# S7G7_footprint_simplified_w_ethernet.net
KiCad netlist of a schematic drawn in EAGLE
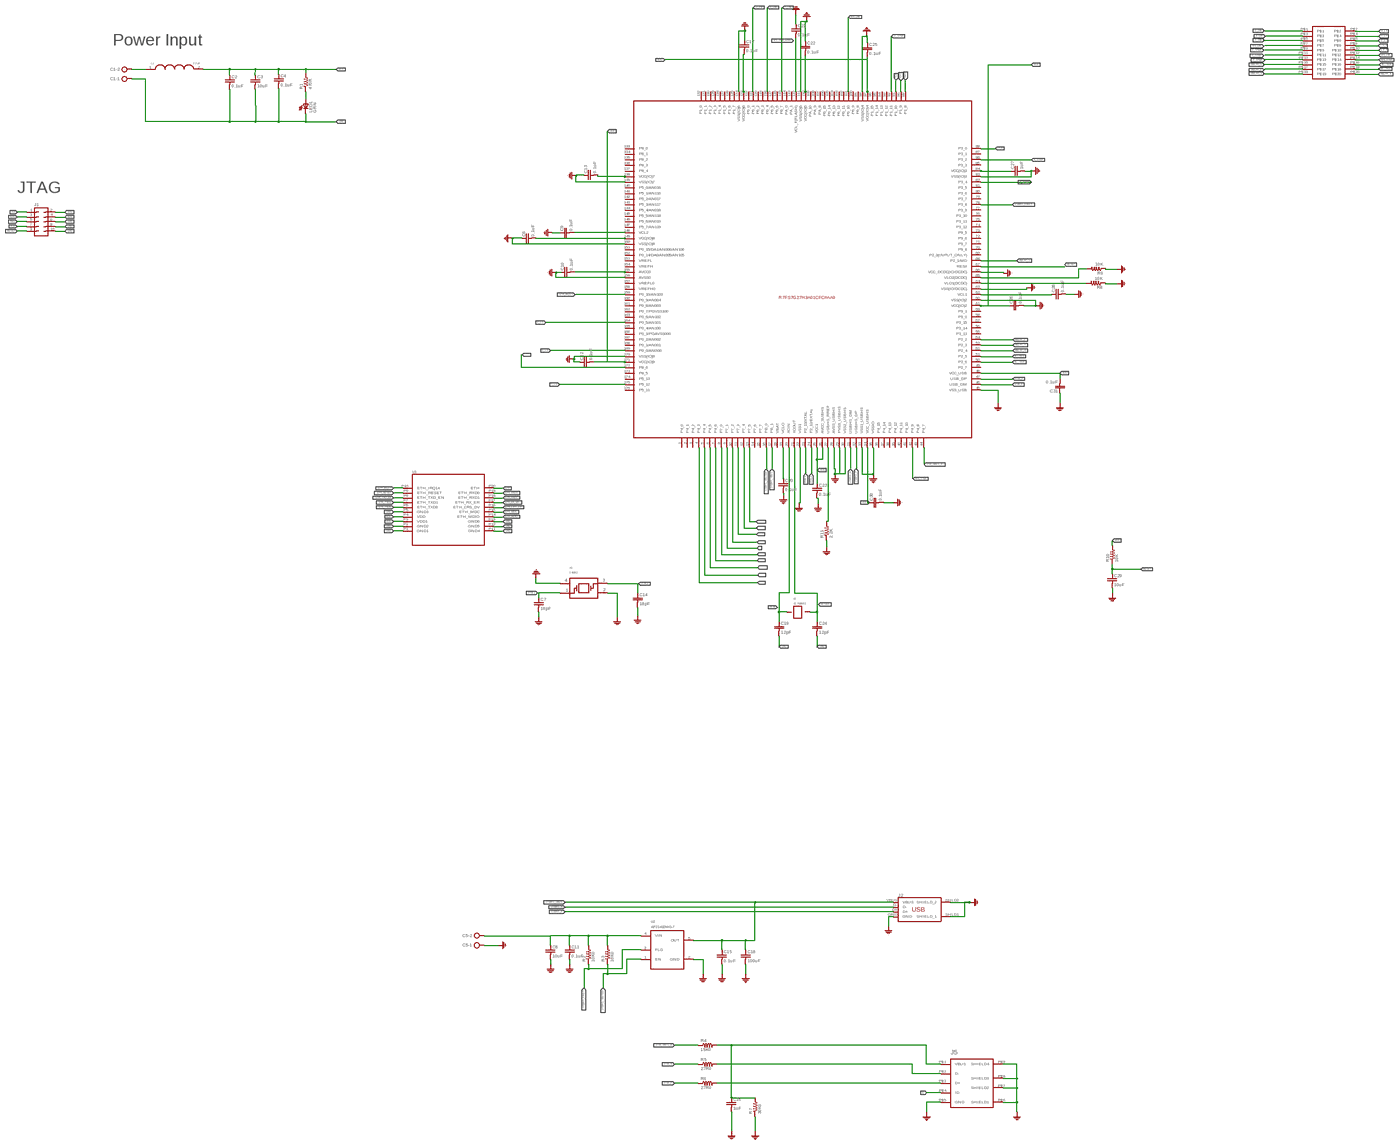
[diagram p0: schematic, sheet 1, overview]
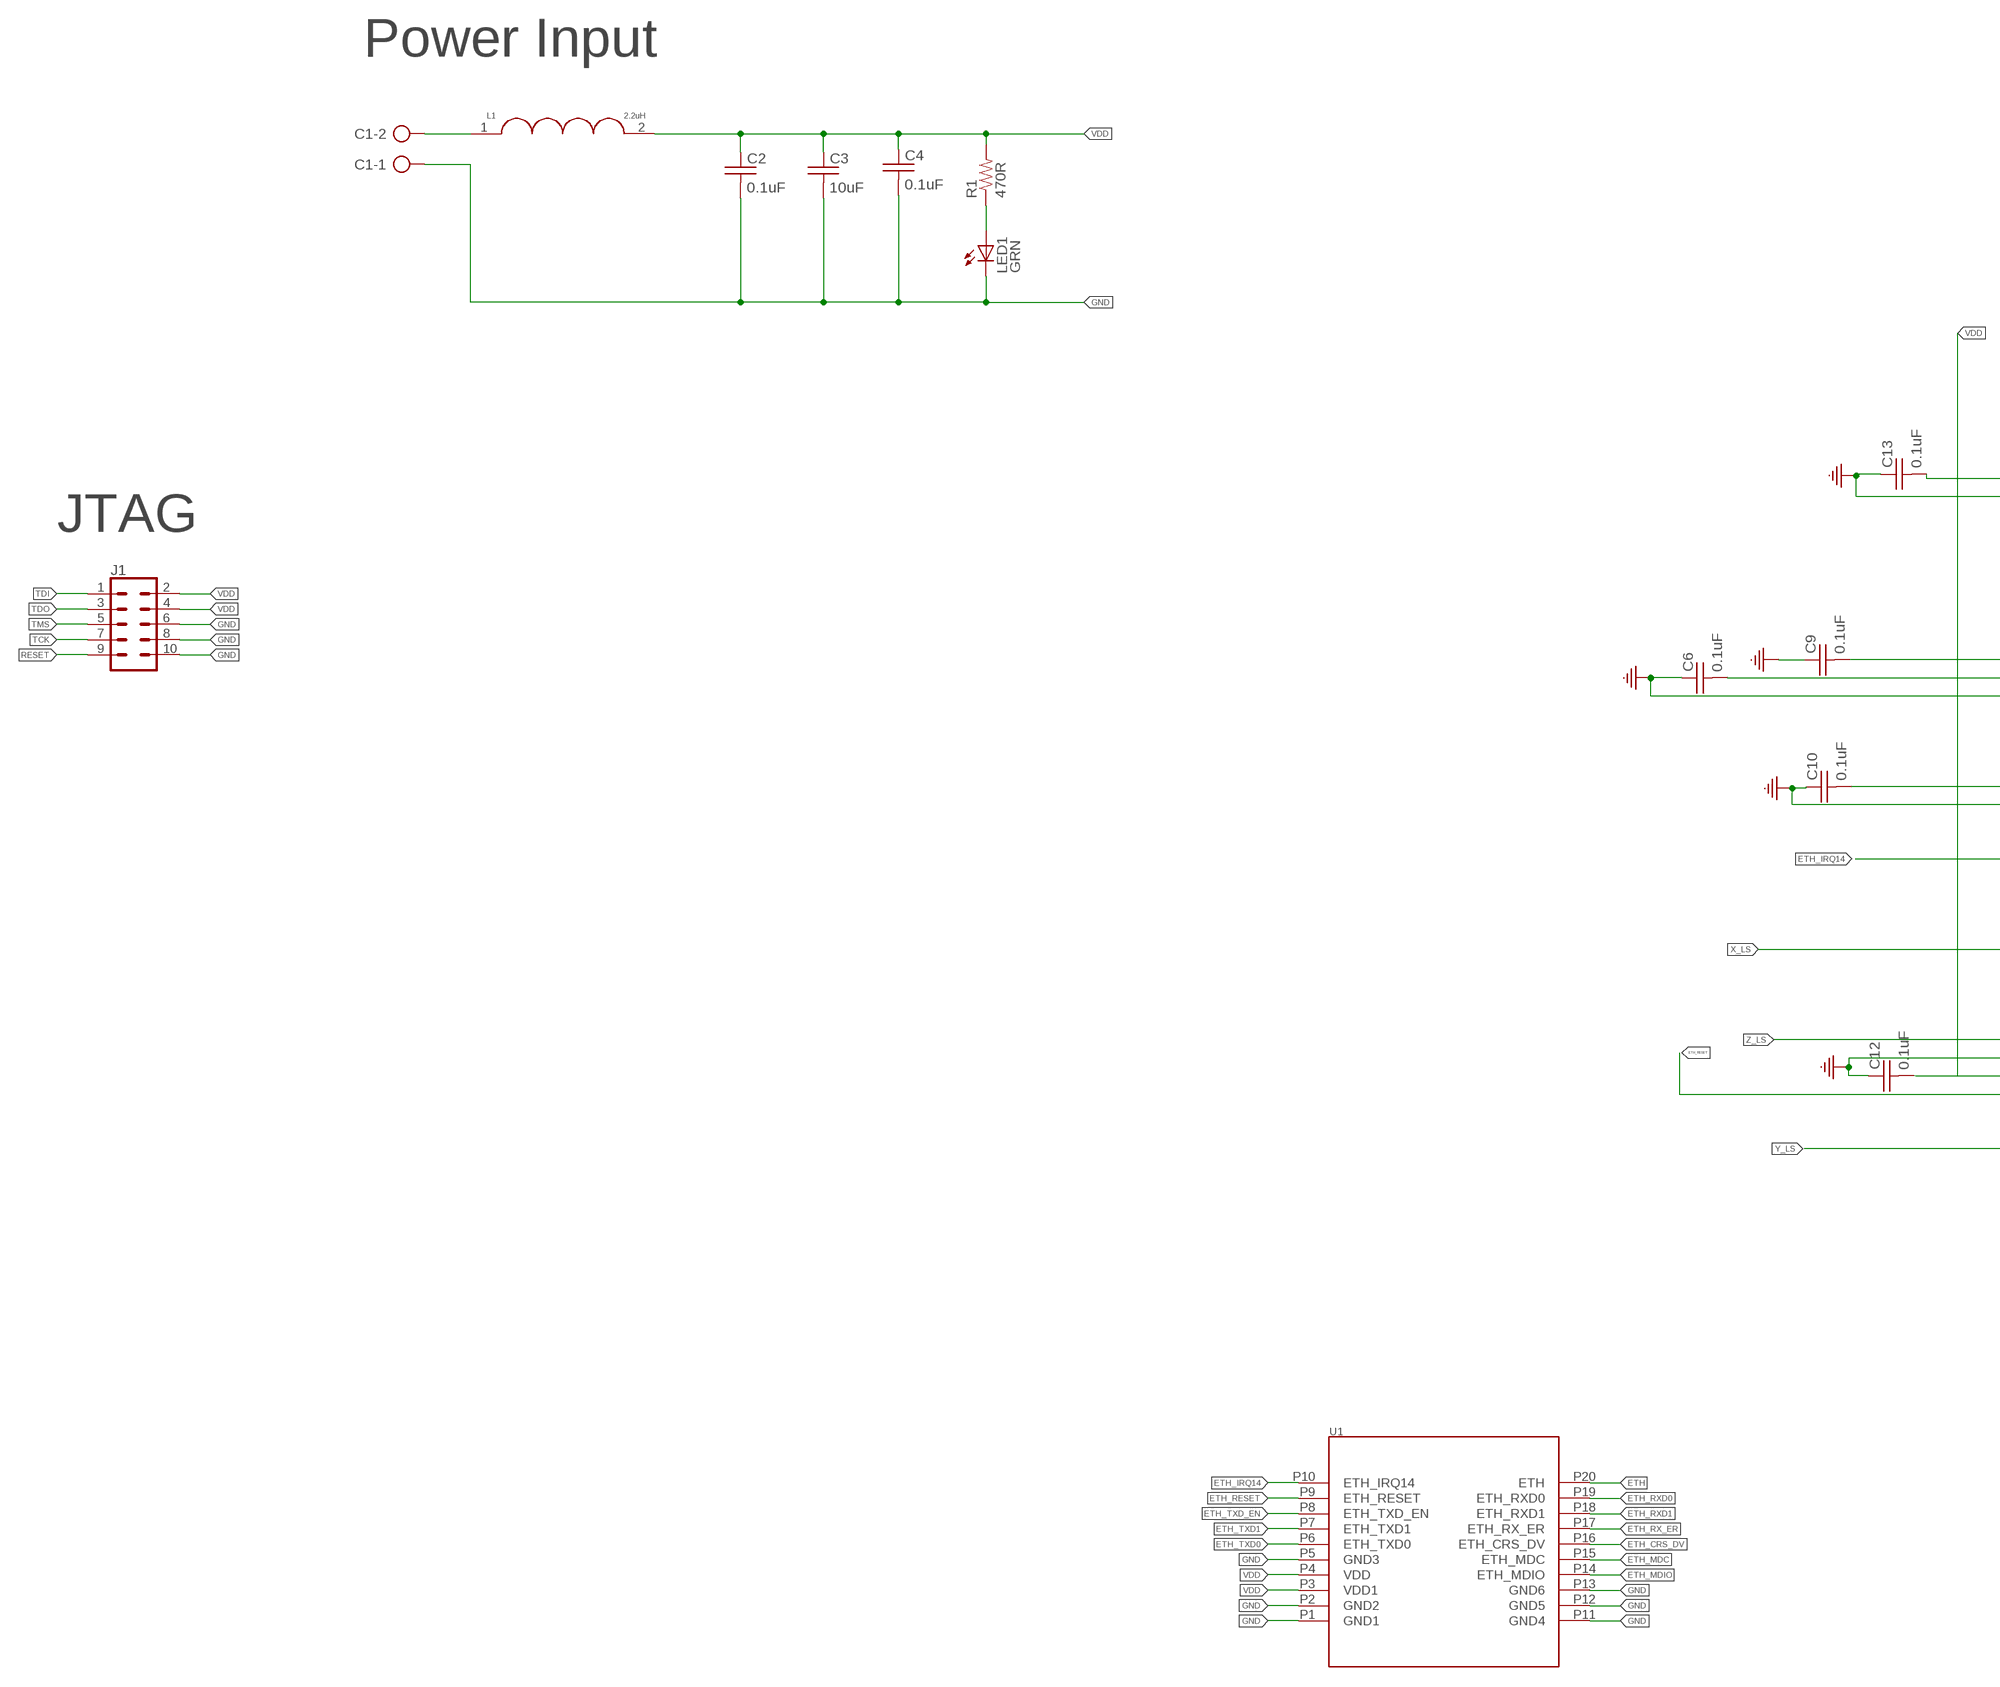
[diagram p1: schematic, sheet 1, part 1 of 4]
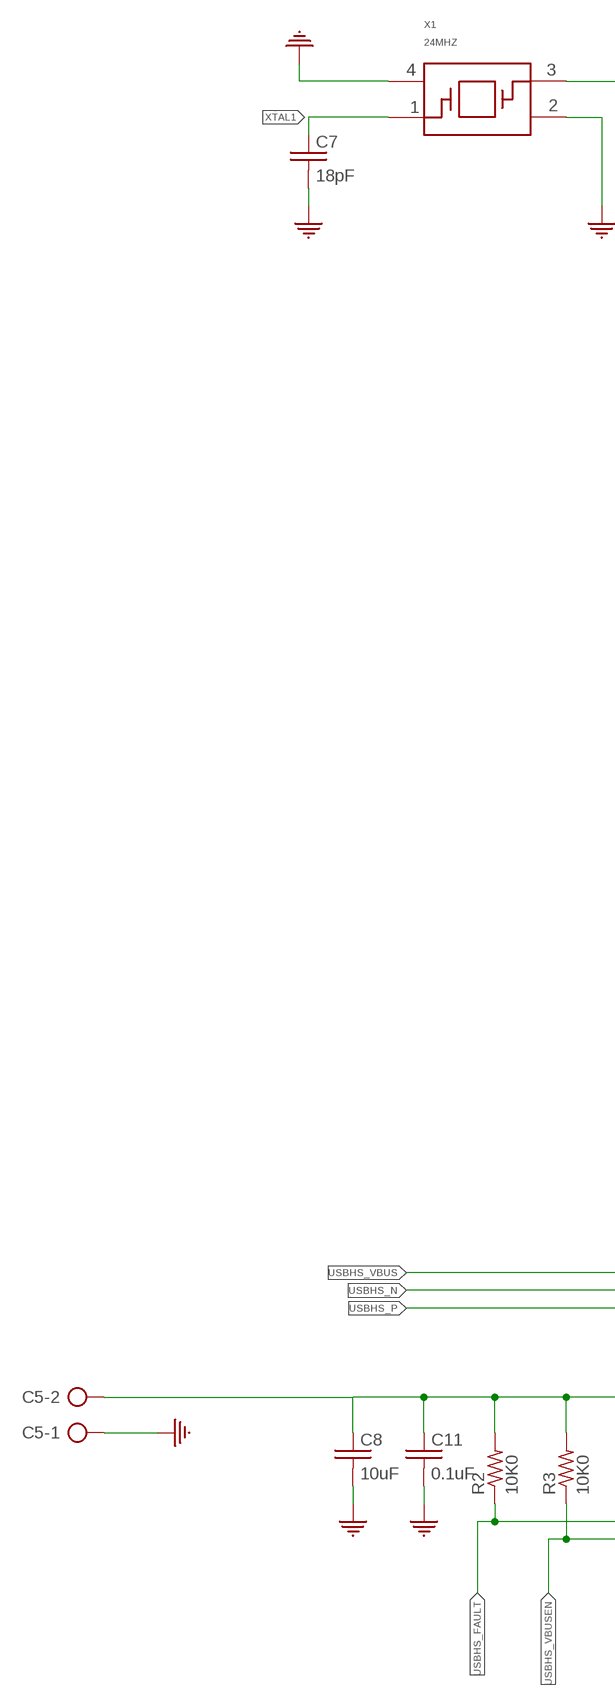
[diagram p2: schematic, sheet 1, part 2 of 4]
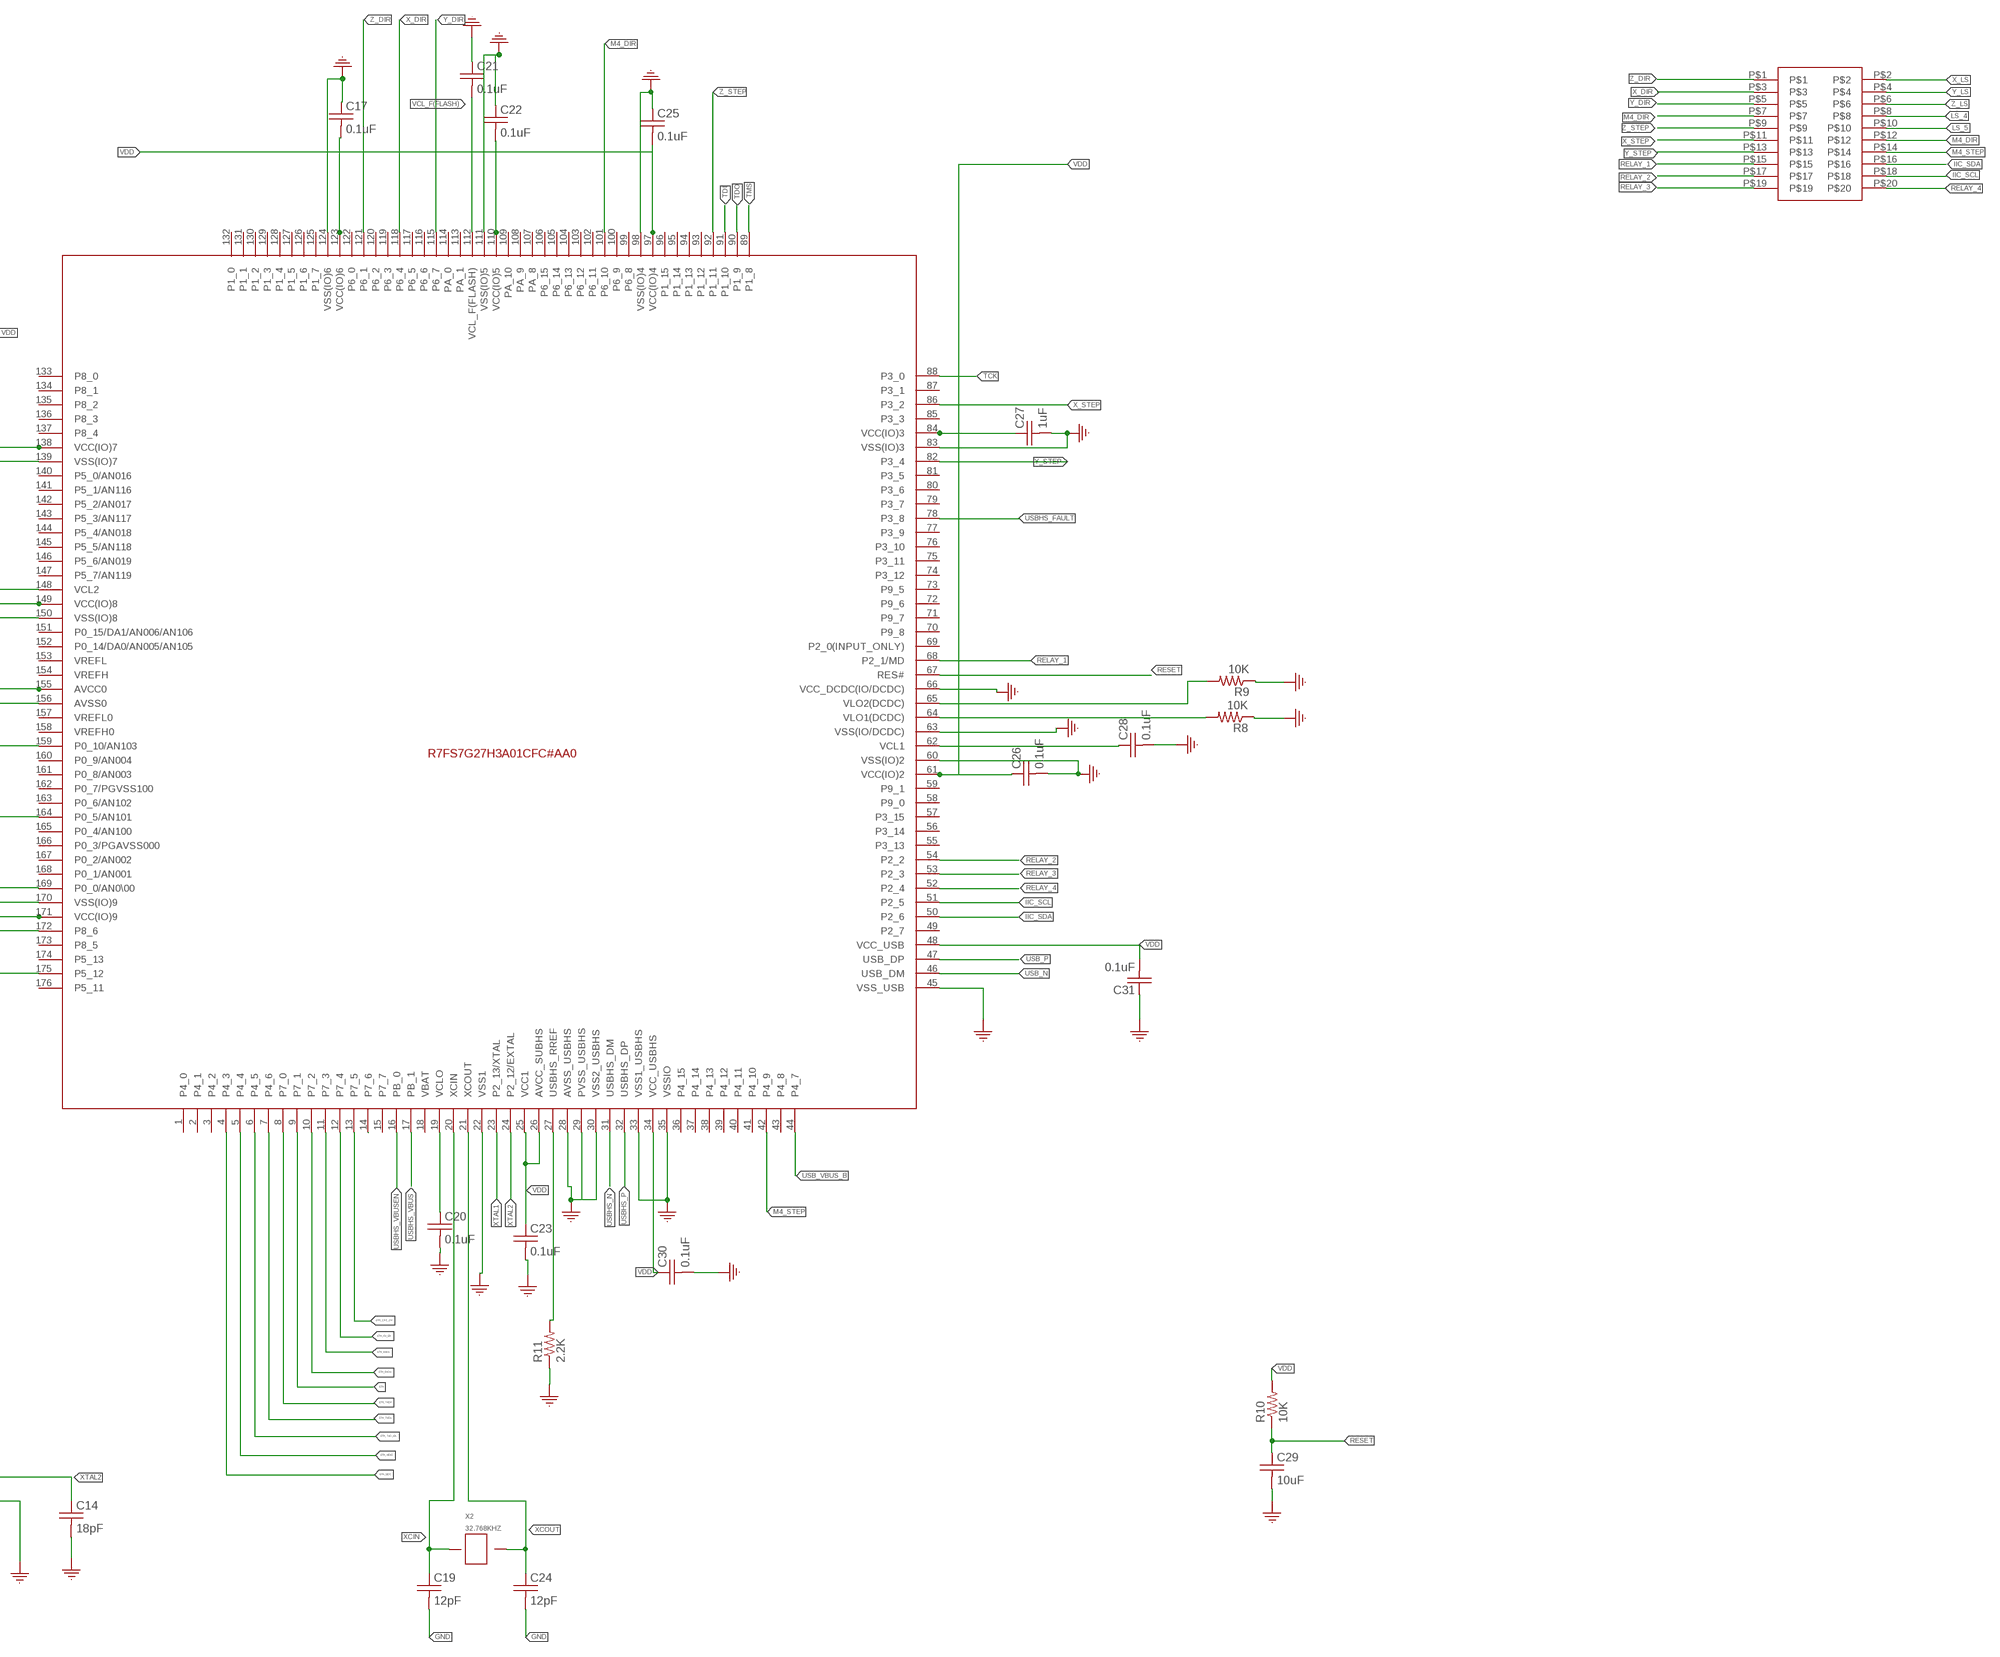
[diagram p3: schematic, sheet 1, part 3 of 4]
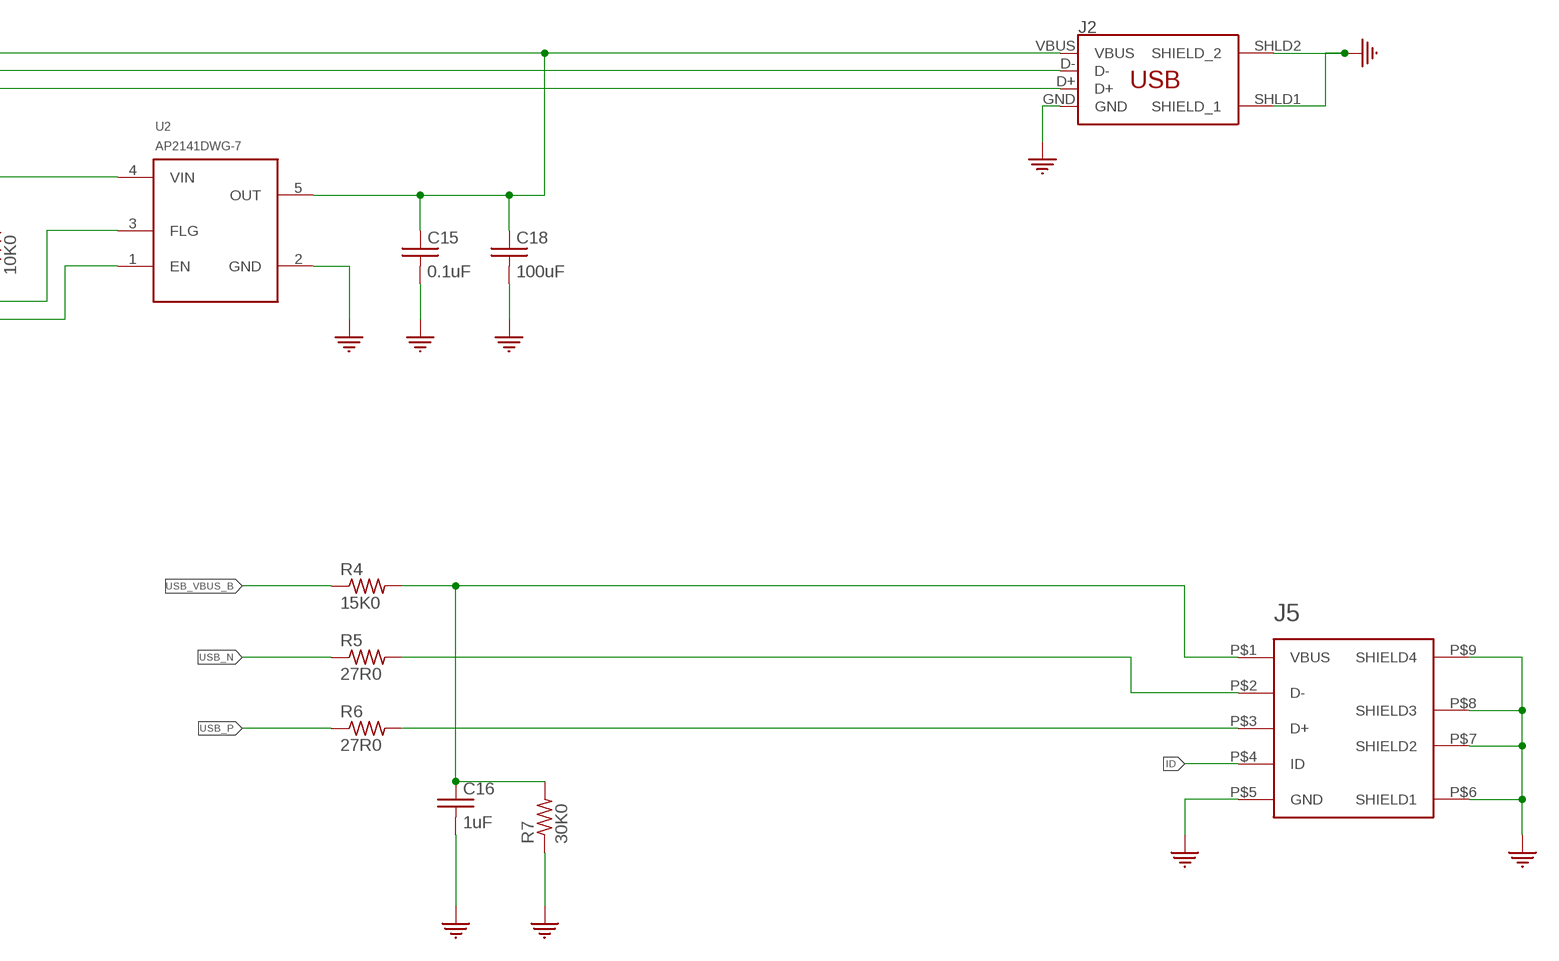
[diagram p4: schematic, sheet 1, part 4 of 4]

(export (version "E")
  (design (tool "Eeschema 10.0.6"))
  (components
    (comp (ref "C1")
      (value "AK300/2")
      (footprint "eagle-import:AK300_2")
      (libsource (lib "eagle-import") (part "AK300/2"))
    )
    (comp (ref "C2")
      (value "0.1uF")
      (footprint "eagle-import:0402")
      (libsource (lib "eagle-import") (part "C_0402"))
    )
    (comp (ref "C3")
      (value "10uF")
      (footprint "eagle-import:0402")
      (libsource (lib "eagle-import") (part "C_0402"))
    )
    (comp (ref "C4")
      (value "0.1uF")
      (footprint "eagle-import:0402")
      (libsource (lib "eagle-import") (part "C_0402"))
    )
    (comp (ref "C5")
      (value "AK300/2")
      (footprint "eagle-import:AK300_2")
      (libsource (lib "eagle-import") (part "AK300/2"))
    )
    (comp (ref "C6")
      (value "0.1uF")
      (footprint "eagle-import:0402")
      (libsource (lib "eagle-import") (part "C_0402"))
    )
    (comp (ref "C7")
      (value "18pF")
      (footprint "eagle-import:0402")
      (libsource (lib "eagle-import") (part "C_0402"))
    )
    (comp (ref "C8")
      (value "10uF")
      (footprint "eagle-import:0402")
      (libsource (lib "eagle-import") (part "C_0402"))
    )
    (comp (ref "C9")
      (value "0.1uF")
      (footprint "eagle-import:0402")
      (libsource (lib "eagle-import") (part "C_0402"))
    )
    (comp (ref "C10")
      (value "0.1uF")
      (footprint "eagle-import:0402")
      (libsource (lib "eagle-import") (part "C_0402"))
    )
    (comp (ref "C11")
      (value "0.1uF")
      (footprint "eagle-import:0402")
      (libsource (lib "eagle-import") (part "C_0402"))
    )
    (comp (ref "C12")
      (value "0.1uF")
      (footprint "eagle-import:0402")
      (libsource (lib "eagle-import") (part "C_0402"))
    )
    (comp (ref "C13")
      (value "0.1uF")
      (footprint "eagle-import:0402")
      (libsource (lib "eagle-import") (part "C_0402"))
    )
    (comp (ref "C14")
      (value "18pF")
      (footprint "eagle-import:0402")
      (libsource (lib "eagle-import") (part "C_0402"))
    )
    (comp (ref "C15")
      (value "0.1uF")
      (footprint "eagle-import:0402")
      (libsource (lib "eagle-import") (part "C_0402"))
    )
    (comp (ref "C16")
      (value "1uF")
      (footprint "eagle-import:0402")
      (libsource (lib "eagle-import") (part "C_0402"))
    )
    (comp (ref "C17")
      (value "0.1uF")
      (footprint "eagle-import:0402")
      (libsource (lib "eagle-import") (part "C_0402"))
    )
    (comp (ref "C18")
      (value "100uF")
      (footprint "eagle-import:C2917")
      (libsource (lib "eagle-import") (part "C_2917"))
    )
    (comp (ref "C19")
      (value "12pF")
      (footprint "eagle-import:0402")
      (libsource (lib "eagle-import") (part "C_0402"))
    )
    (comp (ref "C20")
      (value "0.1uF")
      (footprint "eagle-import:0402")
      (libsource (lib "eagle-import") (part "C_0402"))
    )
    (comp (ref "C21")
      (value "0.1uF")
      (footprint "eagle-import:0402")
      (libsource (lib "eagle-import") (part "C_0402"))
    )
    (comp (ref "C22")
      (value "0.1uF")
      (footprint "eagle-import:0402")
      (libsource (lib "eagle-import") (part "C_0402"))
    )
    (comp (ref "C23")
      (value "0.1uF")
      (footprint "eagle-import:0402")
      (libsource (lib "eagle-import") (part "C_0402"))
    )
    (comp (ref "C24")
      (value "12pF")
      (footprint "eagle-import:0402")
      (libsource (lib "eagle-import") (part "C_0402"))
    )
    (comp (ref "C25")
      (value "0.1uF")
      (footprint "eagle-import:0402")
      (libsource (lib "eagle-import") (part "C_0402"))
    )
    (comp (ref "C26")
      (value "0.1uF")
      (footprint "eagle-import:0402")
      (libsource (lib "eagle-import") (part "C_0402"))
    )
    (comp (ref "C27")
      (value "1uF")
      (footprint "eagle-import:0402")
      (libsource (lib "eagle-import") (part "C_0402"))
    )
    (comp (ref "C28")
      (value "0.1uF")
      (footprint "eagle-import:0402")
      (libsource (lib "eagle-import") (part "C_0402"))
    )
    (comp (ref "C29")
      (value "10uF")
      (footprint "eagle-import:0402")
      (libsource (lib "eagle-import") (part "C_0402"))
    )
    (comp (ref "C30")
      (value "0.1uF")
      (footprint "eagle-import:0402")
      (libsource (lib "eagle-import") (part "C_0402"))
    )
    (comp (ref "C31")
      (value "0.1uF")
      (footprint "eagle-import:0402")
      (libsource (lib "eagle-import") (part "C_0402"))
    )
    (comp (ref "J1")
      (value "CONN_05X2PTH")
      (footprint "eagle-import:2X5")
      (libsource (lib "eagle-import") (part "CONN_05X2PTH"))
    )
    (comp (ref "J2")
      (value "USB_A")
      (footprint "eagle-import:USB_A_SMT")
      (libsource (lib "eagle-import") (part "USB_A"))
    )
    (comp (ref "J4")
      (value "2_X_10_HEADER_GENERIC")
      (footprint "eagle-import:2_X_10_.1_INCH")
      (libsource (lib "eagle-import") (part "2_X_10_HEADER_GENERIC"))
    )
    (comp (ref "J5")
      (value "USB_MICRO-B")
      (footprint "eagle-import:USB_MICRO-B")
      (libsource (lib "eagle-import") (part "USB_MICRO-B"))
    )
    (comp (ref "L1")
      (value "2.2uH")
      (footprint "eagle-import:1008_(2520_METRIC)")
      (libsource (lib "eagle-import") (part "INDUCTOR_1008_2.2_MH_1.3A"))
    )
    (comp (ref "LED1")
      (value "LED_0805_GREEN")
      (footprint "eagle-import:LED_0805_GREEN")
      (libsource (lib "eagle-import") (part "LED_0805_GREEN"))
    )
    (comp (ref "R1")
      (value "470R")
      (footprint "eagle-import:0402")
      (libsource (lib "eagle-import") (part "R_0402"))
    )
    (comp (ref "R2")
      (value "10K0")
      (footprint "eagle-import:0402")
      (libsource (lib "eagle-import") (part "R_0402"))
    )
    (comp (ref "R3")
      (value "10K0")
      (footprint "eagle-import:0402")
      (libsource (lib "eagle-import") (part "R_0402"))
    )
    (comp (ref "R4")
      (value "15K0")
      (footprint "eagle-import:0402")
      (libsource (lib "eagle-import") (part "R_0402"))
    )
    (comp (ref "R5")
      (value "27R0")
      (footprint "eagle-import:0402")
      (libsource (lib "eagle-import") (part "R_0402"))
    )
    (comp (ref "R6")
      (value "27R0")
      (footprint "eagle-import:0402")
      (libsource (lib "eagle-import") (part "R_0402"))
    )
    (comp (ref "R7")
      (value "30K0")
      (footprint "eagle-import:0402")
      (libsource (lib "eagle-import") (part "R_0402"))
    )
    (comp (ref "R8")
      (value "10K")
      (footprint "eagle-import:0402")
      (libsource (lib "eagle-import") (part "R_0402"))
    )
    (comp (ref "R9")
      (value "10K")
      (footprint "eagle-import:0402")
      (libsource (lib "eagle-import") (part "R_0402"))
    )
    (comp (ref "R10")
      (value "10K")
      (footprint "eagle-import:0402")
      (libsource (lib "eagle-import") (part "R_0402"))
    )
    (comp (ref "R11")
      (value "2.2K")
      (footprint "eagle-import:0402")
      (libsource (lib "eagle-import") (part "R_0402"))
    )
    (comp (ref "U1")
      (value "ETHERNET_HAT")
      (footprint "eagle-import:ETHERNET_HAT")
      (libsource (lib "eagle-import") (part "ETHERNET_HAT"))
    )
    (comp (ref "U2")
      (value "AP2141DWG-5")
      (footprint "eagle-import:SOT-23-5")
      (libsource (lib "eagle-import") (part "AP2141DWG-5"))
    )
    (comp (ref "U5")
      (value "S7G2_X_176")
      (footprint "eagle-import:LQFP176_24X24")
      (libsource (lib "eagle-import") (part "S7G2_X_176"))
    )
    (comp (ref "X1")
      (value "24MHZ")
      (footprint "eagle-import:SMD_3225")
      (libsource (lib "eagle-import") (part "XTAL_24_MHZ"))
    )
    (comp (ref "X2")
      (value "32.768KHZ")
      (footprint "eagle-import:SMD_X_2_PADS")
      (libsource (lib "eagle-import") (part "XTAL_32.768KHZ"))
    )
  )
  (nets
    (net (code "1") (name "ETH") (class "Default")
      (node (ref "U1") (pin "P20") (pinfunction "ETH_P20") (pintype "bidirectional"))
      (node (ref "U5") (pin "9") (pinfunction "P7_1_9") (pintype "bidirectional"))
    )
    (net (code "2") (name "ETH_CRS_DV") (class "Default")
      (node (ref "U1") (pin "P16") (pinfunction "ETH_CRS_DV_P16") (pintype "bidirectional"))
      (node (ref "U5") (pin "13") (pinfunction "P7_5_13") (pintype "bidirectional"))
    )
    (net (code "3") (name "ETH_IRQ14") (class "Default")
      (node (ref "U1") (pin "P10") (pinfunction "ETH_IRQ14_P10") (pintype "bidirectional"))
      (node (ref "U5") (pin "159") (pinfunction "P0_10/AN103_159") (pintype "bidirectional"))
    )
    (net (code "4") (name "ETH_MDC") (class "Default")
      (node (ref "U1") (pin "P15") (pinfunction "ETH_MDC_P15") (pintype "bidirectional"))
      (node (ref "U5") (pin "4") (pinfunction "P4_3_4") (pintype "bidirectional"))
    )
    (net (code "5") (name "ETH_MDIO") (class "Default")
      (node (ref "U1") (pin "P14") (pinfunction "ETH_MDIO_P14") (pintype "bidirectional"))
      (node (ref "U5") (pin "5") (pinfunction "P4_4_5") (pintype "bidirectional"))
    )
    (net (code "6") (name "ETH_RESET") (class "Default")
      (node (ref "U1") (pin "P9") (pinfunction "ETH_RESET_P9") (pintype "bidirectional"))
      (node (ref "U5") (pin "172") (pinfunction "P8_6_172") (pintype "bidirectional"))
    )
    (net (code "7") (name "ETH_RXD0") (class "Default")
      (node (ref "U1") (pin "P19") (pinfunction "ETH_RXD0_P19") (pintype "bidirectional"))
      (node (ref "U5") (pin "10") (pinfunction "P7_2_10") (pintype "bidirectional"))
    )
    (net (code "8") (name "ETH_RXD1") (class "Default")
      (node (ref "U1") (pin "P18") (pinfunction "ETH_RXD1_P18") (pintype "bidirectional"))
      (node (ref "U5") (pin "11") (pinfunction "P7_3_11") (pintype "bidirectional"))
    )
    (net (code "9") (name "ETH_RX_ER") (class "Default")
      (node (ref "U1") (pin "P17") (pinfunction "ETH_RX_ER_P17") (pintype "bidirectional"))
      (node (ref "U5") (pin "12") (pinfunction "P7_4_12") (pintype "bidirectional"))
    )
    (net (code "10") (name "ETH_TXD0") (class "Default")
      (node (ref "U1") (pin "P6") (pinfunction "ETH_TXD0_P6") (pintype "bidirectional"))
      (node (ref "U5") (pin "8") (pinfunction "P7_0_8") (pintype "bidirectional"))
    )
    (net (code "11") (name "ETH_TXD1") (class "Default")
      (node (ref "U1") (pin "P7") (pinfunction "ETH_TXD1_P7") (pintype "bidirectional"))
      (node (ref "U5") (pin "7") (pinfunction "P4_6_7") (pintype "bidirectional"))
    )
    (net (code "12") (name "ETH_TXD_EN") (class "Default")
      (node (ref "U1") (pin "P8") (pinfunction "ETH_TXD_EN_P8") (pintype "bidirectional"))
      (node (ref "U5") (pin "6") (pinfunction "P4_5_6") (pintype "bidirectional"))
    )
    (net (code "13") (name "GND") (class "Default")
      (node (ref "C1") (pin "1") (pinfunction "KL_1") (pintype "passive"))
      (node (ref "C10") (pin "P$1") (pinfunction "1_P$1") (pintype "passive"))
      (node (ref "C11") (pin "P$2") (pinfunction "2_P$2") (pintype "passive"))
      (node (ref "C12") (pin "P$1") (pinfunction "1_P$1") (pintype "passive"))
      (node (ref "C13") (pin "P$1") (pinfunction "1_P$1") (pintype "passive"))
      (node (ref "C14") (pin "P$2") (pinfunction "2_P$2") (pintype "passive"))
      (node (ref "C15") (pin "P$2") (pinfunction "2_P$2") (pintype "passive"))
      (node (ref "C16") (pin "P$2") (pinfunction "2_P$2") (pintype "passive"))
      (node (ref "C17") (pin "P$1") (pinfunction "1_P$1") (pintype "passive"))
      (node (ref "C18") (pin "2") (pinfunction "2_2") (pintype "passive"))
      (node (ref "C19") (pin "P$2") (pinfunction "2_P$2") (pintype "passive"))
      (node (ref "C2") (pin "P$2") (pinfunction "2_P$2") (pintype "passive"))
      (node (ref "C20") (pin "P$2") (pinfunction "2_P$2") (pintype "passive"))
      (node (ref "C21") (pin "P$1") (pinfunction "1_P$1") (pintype "passive"))
      (node (ref "C22") (pin "P$1") (pinfunction "1_P$1") (pintype "passive"))
      (node (ref "C23") (pin "P$2") (pinfunction "2_P$2") (pintype "passive"))
      (node (ref "C24") (pin "P$2") (pinfunction "2_P$2") (pintype "passive"))
      (node (ref "C25") (pin "P$1") (pinfunction "1_P$1") (pintype "passive"))
      (node (ref "C26") (pin "P$2") (pinfunction "2_P$2") (pintype "passive"))
      (node (ref "C27") (pin "P$2") (pinfunction "2_P$2") (pintype "passive"))
      (node (ref "C28") (pin "P$2") (pinfunction "2_P$2") (pintype "passive"))
      (node (ref "C29") (pin "P$2") (pinfunction "2_P$2") (pintype "passive"))
      (node (ref "C3") (pin "P$2") (pinfunction "2_P$2") (pintype "passive"))
      (node (ref "C30") (pin "P$2") (pinfunction "2_P$2") (pintype "passive"))
      (node (ref "C31") (pin "P$1") (pinfunction "1_P$1") (pintype "passive"))
      (node (ref "C4") (pin "P$2") (pinfunction "2_P$2") (pintype "passive"))
      (node (ref "C5") (pin "1") (pinfunction "KL_1") (pintype "passive"))
      (node (ref "C6") (pin "P$1") (pinfunction "1_P$1") (pintype "passive"))
      (node (ref "C7") (pin "P$2") (pinfunction "2_P$2") (pintype "passive"))
      (node (ref "C8") (pin "P$2") (pinfunction "2_P$2") (pintype "passive"))
      (node (ref "C9") (pin "P$1") (pinfunction "1_P$1") (pintype "passive"))
      (node (ref "J1") (pin "10") (pinfunction "10_10") (pintype "passive"))
      (node (ref "J1") (pin "6") (pinfunction "6_6") (pintype "passive"))
      (node (ref "J1") (pin "8") (pinfunction "8_8") (pintype "passive"))
      (node (ref "J2") (pin "GND") (pinfunction "GND_GND") (pintype "power_in"))
      (node (ref "J2") (pin "SHLD1") (pinfunction "SHIELD_1_SHLD1") (pintype "bidirectional"))
      (node (ref "J2") (pin "SHLD2") (pinfunction "SHIELD_2_SHLD2") (pintype "bidirectional"))
      (node (ref "J5") (pin "P$5") (pinfunction "GND_P$5") (pintype "bidirectional"))
      (node (ref "J5") (pin "P$6") (pinfunction "SHIELD1_P$6") (pintype "bidirectional"))
      (node (ref "J5") (pin "P$7") (pinfunction "SHIELD2_P$7") (pintype "bidirectional"))
      (node (ref "J5") (pin "P$8") (pinfunction "SHIELD3_P$8") (pintype "bidirectional"))
      (node (ref "J5") (pin "P$9") (pinfunction "SHIELD4_P$9") (pintype "bidirectional"))
      (node (ref "LED1") (pin "C") (pinfunction "C_C") (pintype "passive"))
      (node (ref "R11") (pin "P$1") (pinfunction "1_P$1") (pintype "passive"))
      (node (ref "R7") (pin "P$1") (pinfunction "1_P$1") (pintype "passive"))
      (node (ref "R8") (pin "P$1") (pinfunction "1_P$1") (pintype "passive"))
      (node (ref "R9") (pin "P$1") (pinfunction "1_P$1") (pintype "passive"))
      (node (ref "U1") (pin "P1") (pinfunction "GND1_P1") (pintype "bidirectional"))
      (node (ref "U1") (pin "P11") (pinfunction "GND4_P11") (pintype "bidirectional"))
      (node (ref "U1") (pin "P12") (pinfunction "GND5_P12") (pintype "bidirectional"))
      (node (ref "U1") (pin "P13") (pinfunction "GND6_P13") (pintype "bidirectional"))
      (node (ref "U1") (pin "P2") (pinfunction "GND2_P2") (pintype "bidirectional"))
      (node (ref "U1") (pin "P5") (pinfunction "GND3_P5") (pintype "bidirectional"))
      (node (ref "U2") (pin "2") (pinfunction "GND_2") (pintype "input"))
      (node (ref "U5") (pin "111") (pinfunction "VSS(IO)5_111") (pintype "bidirectional"))
      (node (ref "U5") (pin "124") (pinfunction "VSS(IO)6_124") (pintype "bidirectional"))
      (node (ref "U5") (pin "139") (pinfunction "VSS(IO)7_139") (pintype "bidirectional"))
      (node (ref "U5") (pin "150") (pinfunction "VSS(IO)8_150") (pintype "bidirectional"))
      (node (ref "U5") (pin "156") (pinfunction "AVSS0_156") (pintype "bidirectional"))
      (node (ref "U5") (pin "170") (pinfunction "VSS(IO)9_170") (pintype "bidirectional"))
      (node (ref "U5") (pin "22") (pinfunction "VSS1_22") (pintype "bidirectional"))
      (node (ref "U5") (pin "28") (pinfunction "AVSS_USBHS_28") (pintype "bidirectional"))
      (node (ref "U5") (pin "29") (pinfunction "PVSS_USBHS_29") (pintype "bidirectional"))
      (node (ref "U5") (pin "30") (pinfunction "VSS2_USBHS_30") (pintype "bidirectional"))
      (node (ref "U5") (pin "33") (pinfunction "VSS1_USBHS_33") (pintype "bidirectional"))
      (node (ref "U5") (pin "35") (pinfunction "VSSIO_35") (pintype "bidirectional"))
      (node (ref "U5") (pin "45") (pinfunction "VSS_USB_45") (pintype "bidirectional"))
      (node (ref "U5") (pin "60") (pinfunction "VSS(IO)2_60") (pintype "bidirectional"))
      (node (ref "U5") (pin "63") (pinfunction "VSS(IO/DCDC)_63") (pintype "bidirectional"))
      (node (ref "U5") (pin "66") (pinfunction "VCC_DCDC(IO/DCDC)_66") (pintype "bidirectional"))
      (node (ref "U5") (pin "83") (pinfunction "VSS(IO)3_83") (pintype "bidirectional"))
      (node (ref "U5") (pin "98") (pinfunction "VSS(IO)4_98") (pintype "bidirectional"))
      (node (ref "X1") (pin "2") (pinfunction "2_2") (pintype "bidirectional"))
      (node (ref "X1") (pin "4") (pinfunction "4_4") (pintype "bidirectional"))
    )
    (net (code "14") (name "ID") (class "Default")
      (node (ref "J5") (pin "P$4") (pinfunction "ID_P$4") (pintype "bidirectional"))
    )
    (net (code "15") (name "IIC_SCL") (class "Default")
      (node (ref "J4") (pin "P$18") (pinfunction "P$18_P$18") (pintype "bidirectional"))
      (node (ref "U5") (pin "51") (pinfunction "P2_5_51") (pintype "bidirectional"))
    )
    (net (code "16") (name "IIC_SDA") (class "Default")
      (node (ref "J4") (pin "P$16") (pinfunction "P$16_P$16") (pintype "bidirectional"))
      (node (ref "U5") (pin "50") (pinfunction "P2_6_50") (pintype "bidirectional"))
    )
    (net (code "17") (name "LS_4") (class "Default")
      (node (ref "J4") (pin "P$8") (pinfunction "P$8_P$8") (pintype "bidirectional"))
    )
    (net (code "18") (name "LS_5") (class "Default")
      (node (ref "J4") (pin "P$10") (pinfunction "P$10_P$10") (pintype "bidirectional"))
    )
    (net (code "19") (name "M4_DIR") (class "Default")
      (node (ref "J4") (pin "P$12") (pinfunction "P$12_P$12") (pintype "bidirectional"))
      (node (ref "J4") (pin "P$7") (pinfunction "P$7_P$7") (pintype "bidirectional"))
      (node (ref "U5") (pin "101") (pinfunction "P6_10_101") (pintype "bidirectional"))
    )
    (net (code "20") (name "M4_STEP") (class "Default")
      (node (ref "J4") (pin "P$14") (pinfunction "P$14_P$14") (pintype "bidirectional"))
      (node (ref "U5") (pin "42") (pinfunction "P4_9_42") (pintype "bidirectional"))
    )
    (net (code "21") (name "Net-(C1B-KL)") (class "Default")
      (node (ref "C1") (pin "2") (pinfunction "KL_2") (pintype "passive"))
      (node (ref "L1") (pin "1") (pinfunction "P$1_1") (pintype "bidirectional"))
    )
    (net (code "22") (name "Net-(C9-2)") (class "Default")
      (node (ref "C9") (pin "P$2") (pinfunction "2_P$2") (pintype "passive"))
      (node (ref "U5") (pin "148") (pinfunction "VCL2_148") (pintype "bidirectional"))
    )
    (net (code "23") (name "Net-(C11-1)") (class "Default")
      (node (ref "C11") (pin "P$1") (pinfunction "1_P$1") (pintype "passive"))
      (node (ref "C5") (pin "2") (pinfunction "KL_2") (pintype "passive"))
      (node (ref "C8") (pin "P$1") (pinfunction "1_P$1") (pintype "passive"))
      (node (ref "R2") (pin "P$2") (pinfunction "2_P$2") (pintype "passive"))
      (node (ref "R3") (pin "P$2") (pinfunction "2_P$2") (pintype "passive"))
      (node (ref "U2") (pin "4") (pinfunction "VIN_4") (pintype "input"))
    )
    (net (code "24") (name "Net-(C16-1)") (class "Default")
      (node (ref "C16") (pin "P$1") (pinfunction "1_P$1") (pintype "passive"))
      (node (ref "J5") (pin "P$1") (pinfunction "VBUS_P$1") (pintype "bidirectional"))
      (node (ref "R4") (pin "P$2") (pinfunction "2_P$2") (pintype "passive"))
      (node (ref "R7") (pin "P$2") (pinfunction "2_P$2") (pintype "passive"))
    )
    (net (code "25") (name "Net-(C20-1)") (class "Default")
      (node (ref "C20") (pin "P$1") (pinfunction "1_P$1") (pintype "passive"))
      (node (ref "U5") (pin "19") (pinfunction "VCLO_19") (pintype "bidirectional"))
    )
    (net (code "26") (name "Net-(C28-1)") (class "Default")
      (node (ref "C28") (pin "P$1") (pinfunction "1_P$1") (pintype "passive"))
      (node (ref "U5") (pin "62") (pinfunction "VCL1_62") (pintype "bidirectional"))
    )
    (net (code "27") (name "Net-(J5-D+)") (class "Default")
      (node (ref "J5") (pin "P$3") (pinfunction "D+_P$3") (pintype "bidirectional"))
      (node (ref "R6") (pin "P$2") (pinfunction "2_P$2") (pintype "passive"))
    )
    (net (code "28") (name "Net-(J5-D-)") (class "Default")
      (node (ref "J5") (pin "P$2") (pinfunction "D-_P$2") (pintype "bidirectional"))
      (node (ref "R5") (pin "P$2") (pinfunction "2_P$2") (pintype "passive"))
    )
    (net (code "29") (name "Net-(R1-1)") (class "Default")
      (node (ref "LED1") (pin "A") (pinfunction "A_A") (pintype "passive"))
      (node (ref "R1") (pin "P$1") (pinfunction "1_P$1") (pintype "passive"))
    )
    (net (code "30") (name "Net-(R8-2)") (class "Default")
      (node (ref "R8") (pin "P$2") (pinfunction "2_P$2") (pintype "passive"))
      (node (ref "U5") (pin "64") (pinfunction "VLO1(DCDC)_64") (pintype "bidirectional"))
    )
    (net (code "31") (name "Net-(R9-2)") (class "Default")
      (node (ref "R9") (pin "P$2") (pinfunction "2_P$2") (pintype "passive"))
      (node (ref "U5") (pin "65") (pinfunction "VLO2(DCDC)_65") (pintype "bidirectional"))
    )
    (net (code "32") (name "Net-(R11-2)") (class "Default")
      (node (ref "R11") (pin "P$2") (pinfunction "2_P$2") (pintype "passive"))
      (node (ref "U5") (pin "27") (pinfunction "USBHS_RREF_27") (pintype "bidirectional"))
    )
    (net (code "33") (name "RELAY_1") (class "Default")
      (node (ref "J4") (pin "P$15") (pinfunction "P$15_P$15") (pintype "bidirectional"))
      (node (ref "U5") (pin "68") (pinfunction "P2_1/MD_68") (pintype "bidirectional"))
    )
    (net (code "34") (name "RELAY_2") (class "Default")
      (node (ref "J4") (pin "P$17") (pinfunction "P$17_P$17") (pintype "bidirectional"))
      (node (ref "U5") (pin "54") (pinfunction "P2_2_54") (pintype "bidirectional"))
    )
    (net (code "35") (name "RELAY_3") (class "Default")
      (node (ref "J4") (pin "P$19") (pinfunction "P$19_P$19") (pintype "bidirectional"))
      (node (ref "U5") (pin "53") (pinfunction "P2_3_53") (pintype "bidirectional"))
    )
    (net (code "36") (name "RELAY_4") (class "Default")
      (node (ref "J4") (pin "P$20") (pinfunction "P$20_P$20") (pintype "bidirectional"))
      (node (ref "U5") (pin "52") (pinfunction "P2_4_52") (pintype "bidirectional"))
    )
    (net (code "37") (name "RESET") (class "Default")
      (node (ref "C29") (pin "P$1") (pinfunction "1_P$1") (pintype "passive"))
      (node (ref "J1") (pin "9") (pinfunction "9_9") (pintype "passive"))
      (node (ref "R10") (pin "P$1") (pinfunction "1_P$1") (pintype "passive"))
      (node (ref "U5") (pin "67") (pinfunction "RES#_67") (pintype "bidirectional"))
    )
    (net (code "38") (name "TCK") (class "Default")
      (node (ref "J1") (pin "7") (pinfunction "7_7") (pintype "passive"))
      (node (ref "U5") (pin "88") (pinfunction "P3_0_88") (pintype "bidirectional"))
    )
    (net (code "39") (name "TDI") (class "Default")
      (node (ref "J1") (pin "1") (pinfunction "1_1") (pintype "passive"))
      (node (ref "U5") (pin "91") (pinfunction "P1_10_91") (pintype "bidirectional"))
    )
    (net (code "40") (name "TDO") (class "Default")
      (node (ref "J1") (pin "3") (pinfunction "3_3") (pintype "passive"))
      (node (ref "U5") (pin "90") (pinfunction "P1_9_90") (pintype "bidirectional"))
    )
    (net (code "41") (name "TMS") (class "Default")
      (node (ref "J1") (pin "5") (pinfunction "5_5") (pintype "passive"))
      (node (ref "U5") (pin "89") (pinfunction "P1_8_89") (pintype "bidirectional"))
    )
    (net (code "42") (name "USBHS_FAULT") (class "Default")
      (node (ref "R2") (pin "P$1") (pinfunction "1_P$1") (pintype "passive"))
      (node (ref "U2") (pin "3") (pinfunction "FLG_3") (pintype "input"))
      (node (ref "U5") (pin "78") (pinfunction "P3_8_78") (pintype "bidirectional"))
    )
    (net (code "43") (name "USBHS_N") (class "Default")
      (node (ref "J2") (pin "D-") (pinfunction "D-_D-") (pintype "bidirectional"))
      (node (ref "U5") (pin "31") (pinfunction "USBHS_DM_31") (pintype "bidirectional"))
    )
    (net (code "44") (name "USBHS_P") (class "Default")
      (node (ref "J2") (pin "D+") (pinfunction "D+_D+") (pintype "bidirectional"))
      (node (ref "U5") (pin "32") (pinfunction "USBHS_DP_32") (pintype "bidirectional"))
    )
    (net (code "45") (name "USBHS_VBUS") (class "Default")
      (node (ref "C15") (pin "P$1") (pinfunction "1_P$1") (pintype "passive"))
      (node (ref "C18") (pin "1") (pinfunction "1_1") (pintype "passive"))
      (node (ref "J2") (pin "VBUS") (pinfunction "VBUS_VBUS") (pintype "power_in"))
      (node (ref "U2") (pin "5") (pinfunction "OUT_5") (pintype "input"))
      (node (ref "U5") (pin "17") (pinfunction "PB_1_17") (pintype "bidirectional"))
    )
    (net (code "46") (name "USBHS_VBUSEN") (class "Default")
      (node (ref "R3") (pin "P$1") (pinfunction "1_P$1") (pintype "passive"))
      (node (ref "U2") (pin "1") (pinfunction "EN_1") (pintype "input"))
      (node (ref "U5") (pin "16") (pinfunction "PB_0_16") (pintype "bidirectional"))
    )
    (net (code "47") (name "USB_N") (class "Default")
      (node (ref "R5") (pin "P$1") (pinfunction "1_P$1") (pintype "passive"))
      (node (ref "U5") (pin "46") (pinfunction "USB_DM_46") (pintype "bidirectional"))
    )
    (net (code "48") (name "USB_P") (class "Default")
      (node (ref "R6") (pin "P$1") (pinfunction "1_P$1") (pintype "passive"))
      (node (ref "U5") (pin "47") (pinfunction "USB_DP_47") (pintype "bidirectional"))
    )
    (net (code "49") (name "USB_VBUS_B") (class "Default")
      (node (ref "R4") (pin "P$1") (pinfunction "1_P$1") (pintype "passive"))
      (node (ref "U5") (pin "44") (pinfunction "P4_7_44") (pintype "bidirectional"))
    )
    (net (code "50") (name "VCL_F(FLASH)") (class "Default")
      (node (ref "C21") (pin "P$2") (pinfunction "2_P$2") (pintype "passive"))
      (node (ref "U5") (pin "112") (pinfunction "VCL_F(FLASH)_112") (pintype "bidirectional"))
    )
    (net (code "51") (name "VDD") (class "Default")
      (node (ref "C10") (pin "P$2") (pinfunction "2_P$2") (pintype "passive"))
      (node (ref "C12") (pin "P$2") (pinfunction "2_P$2") (pintype "passive"))
      (node (ref "C13") (pin "P$2") (pinfunction "2_P$2") (pintype "passive"))
      (node (ref "C17") (pin "P$2") (pinfunction "2_P$2") (pintype "passive"))
      (node (ref "C2") (pin "P$1") (pinfunction "1_P$1") (pintype "passive"))
      (node (ref "C22") (pin "P$2") (pinfunction "2_P$2") (pintype "passive"))
      (node (ref "C23") (pin "P$1") (pinfunction "1_P$1") (pintype "passive"))
      (node (ref "C25") (pin "P$2") (pinfunction "2_P$2") (pintype "passive"))
      (node (ref "C26") (pin "P$1") (pinfunction "1_P$1") (pintype "passive"))
      (node (ref "C27") (pin "P$1") (pinfunction "1_P$1") (pintype "passive"))
      (node (ref "C3") (pin "P$1") (pinfunction "1_P$1") (pintype "passive"))
      (node (ref "C30") (pin "P$1") (pinfunction "1_P$1") (pintype "passive"))
      (node (ref "C31") (pin "P$2") (pinfunction "2_P$2") (pintype "passive"))
      (node (ref "C4") (pin "P$1") (pinfunction "1_P$1") (pintype "passive"))
      (node (ref "C6") (pin "P$2") (pinfunction "2_P$2") (pintype "passive"))
      (node (ref "J1") (pin "2") (pinfunction "2_2") (pintype "passive"))
      (node (ref "J1") (pin "4") (pinfunction "4_4") (pintype "passive"))
      (node (ref "L1") (pin "2") (pinfunction "P$2_2") (pintype "bidirectional"))
      (node (ref "R1") (pin "P$2") (pinfunction "2_P$2") (pintype "passive"))
      (node (ref "R10") (pin "P$2") (pinfunction "2_P$2") (pintype "passive"))
      (node (ref "U1") (pin "P3") (pinfunction "VDD1_P3") (pintype "bidirectional"))
      (node (ref "U1") (pin "P4") (pinfunction "VDD_P4") (pintype "bidirectional"))
      (node (ref "U5") (pin "110") (pinfunction "VCC(IO)5_110") (pintype "bidirectional"))
      (node (ref "U5") (pin "123") (pinfunction "VCC(IO)6_123") (pintype "bidirectional"))
      (node (ref "U5") (pin "138") (pinfunction "VCC(IO)7_138") (pintype "bidirectional"))
      (node (ref "U5") (pin "149") (pinfunction "VCC(IO)8_149") (pintype "bidirectional"))
      (node (ref "U5") (pin "155") (pinfunction "AVCC0_155") (pintype "bidirectional"))
      (node (ref "U5") (pin "171") (pinfunction "VCC(IO)9_171") (pintype "bidirectional"))
      (node (ref "U5") (pin "25") (pinfunction "VCC1_25") (pintype "bidirectional"))
      (node (ref "U5") (pin "26") (pinfunction "AVCC_SUBHS_26") (pintype "bidirectional"))
      (node (ref "U5") (pin "34") (pinfunction "VCC_USBHS_34") (pintype "bidirectional"))
      (node (ref "U5") (pin "48") (pinfunction "VCC_USB_48") (pintype "bidirectional"))
      (node (ref "U5") (pin "61") (pinfunction "VCC(IO)2_61") (pintype "bidirectional"))
      (node (ref "U5") (pin "84") (pinfunction "VCC(IO)3_84") (pintype "bidirectional"))
      (node (ref "U5") (pin "97") (pinfunction "VCC(IO)4_97") (pintype "bidirectional"))
    )
    (net (code "52") (name "XCIN") (class "Default")
      (node (ref "C19") (pin "P$1") (pinfunction "1_P$1") (pintype "passive"))
      (node (ref "U5") (pin "20") (pinfunction "XCIN_20") (pintype "bidirectional"))
      (node (ref "X2") (pin "P$1") (pinfunction "P$1_P$1") (pintype "bidirectional"))
    )
    (net (code "53") (name "XCOUT") (class "Default")
      (node (ref "C24") (pin "P$1") (pinfunction "1_P$1") (pintype "passive"))
      (node (ref "U5") (pin "21") (pinfunction "XCOUT_21") (pintype "bidirectional"))
      (node (ref "X2") (pin "P$2") (pinfunction "P$2_P$2") (pintype "bidirectional"))
    )
    (net (code "54") (name "XTAL1") (class "Default")
      (node (ref "C7") (pin "P$1") (pinfunction "1_P$1") (pintype "passive"))
      (node (ref "U5") (pin "23") (pinfunction "P2_13/XTAL_23") (pintype "bidirectional"))
      (node (ref "X1") (pin "1") (pinfunction "1_1") (pintype "bidirectional"))
    )
    (net (code "55") (name "XTAL2") (class "Default")
      (node (ref "C14") (pin "P$1") (pinfunction "1_P$1") (pintype "passive"))
      (node (ref "U5") (pin "24") (pinfunction "P2_12/EXTAL_24") (pintype "bidirectional"))
      (node (ref "X1") (pin "3") (pinfunction "3_3") (pintype "bidirectional"))
    )
    (net (code "56") (name "X_DIR") (class "Default")
      (node (ref "J4") (pin "P$3") (pinfunction "P$3_P$3") (pintype "bidirectional"))
      (node (ref "U5") (pin "118") (pinfunction "P6_4_118") (pintype "bidirectional"))
    )
    (net (code "57") (name "X_LS") (class "Default")
      (node (ref "J4") (pin "P$2") (pinfunction "P$2_P$2") (pintype "bidirectional"))
      (node (ref "U5") (pin "164") (pinfunction "P0_5/AN101_164") (pintype "bidirectional"))
    )
    (net (code "58") (name "X_STEP") (class "Default")
      (node (ref "J4") (pin "P$11") (pinfunction "P$11_P$11") (pintype "bidirectional"))
      (node (ref "U5") (pin "86") (pinfunction "P3_2_86") (pintype "bidirectional"))
    )
    (net (code "59") (name "Y_DIR") (class "Default")
      (node (ref "J4") (pin "P$5") (pinfunction "P$5_P$5") (pintype "bidirectional"))
      (node (ref "U5") (pin "115") (pinfunction "P6_7_115") (pintype "bidirectional"))
    )
    (net (code "60") (name "Y_LS") (class "Default")
      (node (ref "J4") (pin "P$4") (pinfunction "P$4_P$4") (pintype "bidirectional"))
      (node (ref "U5") (pin "175") (pinfunction "P5_12_175") (pintype "bidirectional"))
    )
    (net (code "61") (name "Y_STEP") (class "Default")
      (node (ref "J4") (pin "P$13") (pinfunction "P$13_P$13") (pintype "bidirectional"))
      (node (ref "U5") (pin "82") (pinfunction "P3_4_82") (pintype "bidirectional"))
    )
    (net (code "62") (name "Z_DIR") (class "Default")
      (node (ref "J4") (pin "P$1") (pinfunction "P$1_P$1") (pintype "bidirectional"))
      (node (ref "U5") (pin "121") (pinfunction "P6_1_121") (pintype "bidirectional"))
    )
    (net (code "63") (name "Z_LS") (class "Default")
      (node (ref "J4") (pin "P$6") (pinfunction "P$6_P$6") (pintype "bidirectional"))
      (node (ref "U5") (pin "169") (pinfunction "P0_0/AN0\\00_169") (pintype "bidirectional"))
    )
    (net (code "64") (name "Z_STEP") (class "Default")
      (node (ref "J4") (pin "P$9") (pinfunction "P$9_P$9") (pintype "bidirectional"))
      (node (ref "U5") (pin "92") (pinfunction "P1_11_92") (pintype "bidirectional"))
    )
    (net (code "65") (name "unconnected-(U5-P0_1{slash}AN001-Pad168)") (class "Default")
      (node (ref "U5") (pin "168") (pinfunction "P0_1/AN001_168") (pintype "bidirectional"))
    )
    (net (code "66") (name "unconnected-(U5-P0_2{slash}AN002-Pad167)") (class "Default")
      (node (ref "U5") (pin "167") (pinfunction "P0_2/AN002_167") (pintype "bidirectional"))
    )
    (net (code "67") (name "unconnected-(U5-P0_3{slash}PGAVSS000-Pad166)") (class "Default")
      (node (ref "U5") (pin "166") (pinfunction "P0_3/PGAVSS000_166") (pintype "bidirectional"))
    )
    (net (code "68") (name "unconnected-(U5-P0_4{slash}AN100-Pad165)") (class "Default")
      (node (ref "U5") (pin "165") (pinfunction "P0_4/AN100_165") (pintype "bidirectional"))
    )
    (net (code "69") (name "unconnected-(U5-P0_6{slash}AN102-Pad163)") (class "Default")
      (node (ref "U5") (pin "163") (pinfunction "P0_6/AN102_163") (pintype "bidirectional"))
    )
    (net (code "70") (name "unconnected-(U5-P0_7{slash}PGVSS100-Pad162)") (class "Default")
      (node (ref "U5") (pin "162") (pinfunction "P0_7/PGVSS100_162") (pintype "bidirectional"))
    )
    (net (code "71") (name "unconnected-(U5-P0_8{slash}AN003-Pad161)") (class "Default")
      (node (ref "U5") (pin "161") (pinfunction "P0_8/AN003_161") (pintype "bidirectional"))
    )
    (net (code "72") (name "unconnected-(U5-P0_9{slash}AN004-Pad160)") (class "Default")
      (node (ref "U5") (pin "160") (pinfunction "P0_9/AN004_160") (pintype "bidirectional"))
    )
    (net (code "73") (name "unconnected-(U5-P0_14{slash}DA0{slash}AN005{slash}AN105-Pad152)") (class "Default")
      (node (ref "U5") (pin "152") (pinfunction "P0_14/DA0/AN005/AN105_152") (pintype "bidirectional"))
    )
    (net (code "74") (name "unconnected-(U5-P0_15{slash}DA1{slash}AN006{slash}AN106-Pad151)") (class "Default")
      (node (ref "U5") (pin "151") (pinfunction "P0_15/DA1/AN006/AN106_151") (pintype "bidirectional"))
    )
    (net (code "75") (name "unconnected-(U5-P1_0-Pad132)") (class "Default")
      (node (ref "U5") (pin "132") (pinfunction "P1_0_132") (pintype "bidirectional"))
    )
    (net (code "76") (name "unconnected-(U5-P1_1-Pad131)") (class "Default")
      (node (ref "U5") (pin "131") (pinfunction "P1_1_131") (pintype "bidirectional"))
    )
    (net (code "77") (name "unconnected-(U5-P1_2-Pad130)") (class "Default")
      (node (ref "U5") (pin "130") (pinfunction "P1_2_130") (pintype "bidirectional"))
    )
    (net (code "78") (name "unconnected-(U5-P1_3-Pad129)") (class "Default")
      (node (ref "U5") (pin "129") (pinfunction "P1_3_129") (pintype "bidirectional"))
    )
    (net (code "79") (name "unconnected-(U5-P1_4-Pad128)") (class "Default")
      (node (ref "U5") (pin "128") (pinfunction "P1_4_128") (pintype "bidirectional"))
    )
    (net (code "80") (name "unconnected-(U5-P1_5-Pad127)") (class "Default")
      (node (ref "U5") (pin "127") (pinfunction "P1_5_127") (pintype "bidirectional"))
    )
    (net (code "81") (name "unconnected-(U5-P1_6-Pad126)") (class "Default")
      (node (ref "U5") (pin "126") (pinfunction "P1_6_126") (pintype "bidirectional"))
    )
    (net (code "82") (name "unconnected-(U5-P1_7-Pad125)") (class "Default")
      (node (ref "U5") (pin "125") (pinfunction "P1_7_125") (pintype "bidirectional"))
    )
    (net (code "83") (name "unconnected-(U5-P1_12-Pad93)") (class "Default")
      (node (ref "U5") (pin "93") (pinfunction "P1_12_93") (pintype "bidirectional"))
    )
    (net (code "84") (name "unconnected-(U5-P1_13-Pad94)") (class "Default")
      (node (ref "U5") (pin "94") (pinfunction "P1_13_94") (pintype "bidirectional"))
    )
    (net (code "85") (name "unconnected-(U5-P1_14-Pad95)") (class "Default")
      (node (ref "U5") (pin "95") (pinfunction "P1_14_95") (pintype "bidirectional"))
    )
    (net (code "86") (name "unconnected-(U5-P1_15-Pad96)") (class "Default")
      (node (ref "U5") (pin "96") (pinfunction "P1_15_96") (pintype "bidirectional"))
    )
    (net (code "87") (name "unconnected-(U5-P2_0(INPUT_ONLY)-Pad69)") (class "Default")
      (node (ref "U5") (pin "69") (pinfunction "P2_0(INPUT_ONLY)_69") (pintype "bidirectional"))
    )
    (net (code "88") (name "unconnected-(U5-P2_7-Pad49)") (class "Default")
      (node (ref "U5") (pin "49") (pinfunction "P2_7_49") (pintype "bidirectional"))
    )
    (net (code "89") (name "unconnected-(U5-P3_1-Pad87)") (class "Default")
      (node (ref "U5") (pin "87") (pinfunction "P3_1_87") (pintype "bidirectional"))
    )
    (net (code "90") (name "unconnected-(U5-P3_3-Pad85)") (class "Default")
      (node (ref "U5") (pin "85") (pinfunction "P3_3_85") (pintype "bidirectional"))
    )
    (net (code "91") (name "unconnected-(U5-P3_5-Pad81)") (class "Default")
      (node (ref "U5") (pin "81") (pinfunction "P3_5_81") (pintype "bidirectional"))
    )
    (net (code "92") (name "unconnected-(U5-P3_6-Pad80)") (class "Default")
      (node (ref "U5") (pin "80") (pinfunction "P3_6_80") (pintype "bidirectional"))
    )
    (net (code "93") (name "unconnected-(U5-P3_7-Pad79)") (class "Default")
      (node (ref "U5") (pin "79") (pinfunction "P3_7_79") (pintype "bidirectional"))
    )
    (net (code "94") (name "unconnected-(U5-P3_9-Pad77)") (class "Default")
      (node (ref "U5") (pin "77") (pinfunction "P3_9_77") (pintype "bidirectional"))
    )
    (net (code "95") (name "unconnected-(U5-P3_10-Pad76)") (class "Default")
      (node (ref "U5") (pin "76") (pinfunction "P3_10_76") (pintype "bidirectional"))
    )
    (net (code "96") (name "unconnected-(U5-P3_11-Pad75)") (class "Default")
      (node (ref "U5") (pin "75") (pinfunction "P3_11_75") (pintype "bidirectional"))
    )
    (net (code "97") (name "unconnected-(U5-P3_12-Pad74)") (class "Default")
      (node (ref "U5") (pin "74") (pinfunction "P3_12_74") (pintype "bidirectional"))
    )
    (net (code "98") (name "unconnected-(U5-P3_13-Pad55)") (class "Default")
      (node (ref "U5") (pin "55") (pinfunction "P3_13_55") (pintype "bidirectional"))
    )
    (net (code "99") (name "unconnected-(U5-P3_14-Pad56)") (class "Default")
      (node (ref "U5") (pin "56") (pinfunction "P3_14_56") (pintype "bidirectional"))
    )
    (net (code "100") (name "unconnected-(U5-P3_15-Pad57)") (class "Default")
      (node (ref "U5") (pin "57") (pinfunction "P3_15_57") (pintype "bidirectional"))
    )
    (net (code "101") (name "unconnected-(U5-P4_0-Pad1)") (class "Default")
      (node (ref "U5") (pin "1") (pinfunction "P4_0_1") (pintype "bidirectional"))
    )
    (net (code "102") (name "unconnected-(U5-P4_1-Pad2)") (class "Default")
      (node (ref "U5") (pin "2") (pinfunction "P4_1_2") (pintype "bidirectional"))
    )
    (net (code "103") (name "unconnected-(U5-P4_2-Pad3)") (class "Default")
      (node (ref "U5") (pin "3") (pinfunction "P4_2_3") (pintype "bidirectional"))
    )
    (net (code "104") (name "unconnected-(U5-P4_8-Pad43)") (class "Default")
      (node (ref "U5") (pin "43") (pinfunction "P4_8_43") (pintype "bidirectional"))
    )
    (net (code "105") (name "unconnected-(U5-P4_10-Pad41)") (class "Default")
      (node (ref "U5") (pin "41") (pinfunction "P4_10_41") (pintype "bidirectional"))
    )
    (net (code "106") (name "unconnected-(U5-P4_11-Pad40)") (class "Default")
      (node (ref "U5") (pin "40") (pinfunction "P4_11_40") (pintype "bidirectional"))
    )
    (net (code "107") (name "unconnected-(U5-P4_12-Pad39)") (class "Default")
      (node (ref "U5") (pin "39") (pinfunction "P4_12_39") (pintype "bidirectional"))
    )
    (net (code "108") (name "unconnected-(U5-P4_13-Pad38)") (class "Default")
      (node (ref "U5") (pin "38") (pinfunction "P4_13_38") (pintype "bidirectional"))
    )
    (net (code "109") (name "unconnected-(U5-P4_14-Pad37)") (class "Default")
      (node (ref "U5") (pin "37") (pinfunction "P4_14_37") (pintype "bidirectional"))
    )
    (net (code "110") (name "unconnected-(U5-P4_15-Pad36)") (class "Default")
      (node (ref "U5") (pin "36") (pinfunction "P4_15_36") (pintype "bidirectional"))
    )
    (net (code "111") (name "unconnected-(U5-P5_0{slash}AN016-Pad140)") (class "Default")
      (node (ref "U5") (pin "140") (pinfunction "P5_0/AN016_140") (pintype "bidirectional"))
    )
    (net (code "112") (name "unconnected-(U5-P5_1{slash}AN116-Pad141)") (class "Default")
      (node (ref "U5") (pin "141") (pinfunction "P5_1/AN116_141") (pintype "bidirectional"))
    )
    (net (code "113") (name "unconnected-(U5-P5_2{slash}AN017-Pad142)") (class "Default")
      (node (ref "U5") (pin "142") (pinfunction "P5_2/AN017_142") (pintype "bidirectional"))
    )
    (net (code "114") (name "unconnected-(U5-P5_3{slash}AN117-Pad143)") (class "Default")
      (node (ref "U5") (pin "143") (pinfunction "P5_3/AN117_143") (pintype "bidirectional"))
    )
    (net (code "115") (name "unconnected-(U5-P5_4{slash}AN018-Pad144)") (class "Default")
      (node (ref "U5") (pin "144") (pinfunction "P5_4/AN018_144") (pintype "bidirectional"))
    )
    (net (code "116") (name "unconnected-(U5-P5_5{slash}AN118-Pad145)") (class "Default")
      (node (ref "U5") (pin "145") (pinfunction "P5_5/AN118_145") (pintype "bidirectional"))
    )
    (net (code "117") (name "unconnected-(U5-P5_6{slash}AN019-Pad146)") (class "Default")
      (node (ref "U5") (pin "146") (pinfunction "P5_6/AN019_146") (pintype "bidirectional"))
    )
    (net (code "118") (name "unconnected-(U5-P5_7{slash}AN119-Pad147)") (class "Default")
      (node (ref "U5") (pin "147") (pinfunction "P5_7/AN119_147") (pintype "bidirectional"))
    )
    (net (code "119") (name "unconnected-(U5-P5_11-Pad176)") (class "Default")
      (node (ref "U5") (pin "176") (pinfunction "P5_11_176") (pintype "bidirectional"))
    )
    (net (code "120") (name "unconnected-(U5-P5_13-Pad174)") (class "Default")
      (node (ref "U5") (pin "174") (pinfunction "P5_13_174") (pintype "bidirectional"))
    )
    (net (code "121") (name "unconnected-(U5-P6_0-Pad122)") (class "Default")
      (node (ref "U5") (pin "122") (pinfunction "P6_0_122") (pintype "bidirectional"))
    )
    (net (code "122") (name "unconnected-(U5-P6_2-Pad120)") (class "Default")
      (node (ref "U5") (pin "120") (pinfunction "P6_2_120") (pintype "bidirectional"))
    )
    (net (code "123") (name "unconnected-(U5-P6_3-Pad119)") (class "Default")
      (node (ref "U5") (pin "119") (pinfunction "P6_3_119") (pintype "bidirectional"))
    )
    (net (code "124") (name "unconnected-(U5-P6_5-Pad117)") (class "Default")
      (node (ref "U5") (pin "117") (pinfunction "P6_5_117") (pintype "bidirectional"))
    )
    (net (code "125") (name "unconnected-(U5-P6_6-Pad116)") (class "Default")
      (node (ref "U5") (pin "116") (pinfunction "P6_6_116") (pintype "bidirectional"))
    )
    (net (code "126") (name "unconnected-(U5-P6_8-Pad99)") (class "Default")
      (node (ref "U5") (pin "99") (pinfunction "P6_8_99") (pintype "bidirectional"))
    )
    (net (code "127") (name "unconnected-(U5-P6_9-Pad100)") (class "Default")
      (node (ref "U5") (pin "100") (pinfunction "P6_9_100") (pintype "bidirectional"))
    )
    (net (code "128") (name "unconnected-(U5-P6_11-Pad102)") (class "Default")
      (node (ref "U5") (pin "102") (pinfunction "P6_11_102") (pintype "bidirectional"))
    )
    (net (code "129") (name "unconnected-(U5-P6_12-Pad103)") (class "Default")
      (node (ref "U5") (pin "103") (pinfunction "P6_12_103") (pintype "bidirectional"))
    )
    (net (code "130") (name "unconnected-(U5-P6_13-Pad104)") (class "Default")
      (node (ref "U5") (pin "104") (pinfunction "P6_13_104") (pintype "bidirectional"))
    )
    (net (code "131") (name "unconnected-(U5-P6_14-Pad105)") (class "Default")
      (node (ref "U5") (pin "105") (pinfunction "P6_14_105") (pintype "bidirectional"))
    )
    (net (code "132") (name "unconnected-(U5-P6_15-Pad106)") (class "Default")
      (node (ref "U5") (pin "106") (pinfunction "P6_15_106") (pintype "bidirectional"))
    )
    (net (code "133") (name "unconnected-(U5-P7_6-Pad14)") (class "Default")
      (node (ref "U5") (pin "14") (pinfunction "P7_6_14") (pintype "bidirectional"))
    )
    (net (code "134") (name "unconnected-(U5-P7_7-Pad15)") (class "Default")
      (node (ref "U5") (pin "15") (pinfunction "P7_7_15") (pintype "bidirectional"))
    )
    (net (code "135") (name "unconnected-(U5-P8_0-Pad133)") (class "Default")
      (node (ref "U5") (pin "133") (pinfunction "P8_0_133") (pintype "bidirectional"))
    )
    (net (code "136") (name "unconnected-(U5-P8_1-Pad134)") (class "Default")
      (node (ref "U5") (pin "134") (pinfunction "P8_1_134") (pintype "bidirectional"))
    )
    (net (code "137") (name "unconnected-(U5-P8_2-Pad135)") (class "Default")
      (node (ref "U5") (pin "135") (pinfunction "P8_2_135") (pintype "bidirectional"))
    )
    (net (code "138") (name "unconnected-(U5-P8_3-Pad136)") (class "Default")
      (node (ref "U5") (pin "136") (pinfunction "P8_3_136") (pintype "bidirectional"))
    )
    (net (code "139") (name "unconnected-(U5-P8_4-Pad137)") (class "Default")
      (node (ref "U5") (pin "137") (pinfunction "P8_4_137") (pintype "bidirectional"))
    )
    (net (code "140") (name "unconnected-(U5-P8_5-Pad173)") (class "Default")
      (node (ref "U5") (pin "173") (pinfunction "P8_5_173") (pintype "bidirectional"))
    )
    (net (code "141") (name "unconnected-(U5-P9_0-Pad58)") (class "Default")
      (node (ref "U5") (pin "58") (pinfunction "P9_0_58") (pintype "bidirectional"))
    )
    (net (code "142") (name "unconnected-(U5-P9_1-Pad59)") (class "Default")
      (node (ref "U5") (pin "59") (pinfunction "P9_1_59") (pintype "bidirectional"))
    )
    (net (code "143") (name "unconnected-(U5-P9_5-Pad73)") (class "Default")
      (node (ref "U5") (pin "73") (pinfunction "P9_5_73") (pintype "bidirectional"))
    )
    (net (code "144") (name "unconnected-(U5-P9_6-Pad72)") (class "Default")
      (node (ref "U5") (pin "72") (pinfunction "P9_6_72") (pintype "bidirectional"))
    )
    (net (code "145") (name "unconnected-(U5-P9_7-Pad71)") (class "Default")
      (node (ref "U5") (pin "71") (pinfunction "P9_7_71") (pintype "bidirectional"))
    )
    (net (code "146") (name "unconnected-(U5-P9_8-Pad70)") (class "Default")
      (node (ref "U5") (pin "70") (pinfunction "P9_8_70") (pintype "bidirectional"))
    )
    (net (code "147") (name "unconnected-(U5-PA_0-Pad114)") (class "Default")
      (node (ref "U5") (pin "114") (pinfunction "PA_0_114") (pintype "bidirectional"))
    )
    (net (code "148") (name "unconnected-(U5-PA_1-Pad113)") (class "Default")
      (node (ref "U5") (pin "113") (pinfunction "PA_1_113") (pintype "bidirectional"))
    )
    (net (code "149") (name "unconnected-(U5-PA_8-Pad107)") (class "Default")
      (node (ref "U5") (pin "107") (pinfunction "PA_8_107") (pintype "bidirectional"))
    )
    (net (code "150") (name "unconnected-(U5-PA_9-Pad108)") (class "Default")
      (node (ref "U5") (pin "108") (pinfunction "PA_9_108") (pintype "bidirectional"))
    )
    (net (code "151") (name "unconnected-(U5-PA_10-Pad109)") (class "Default")
      (node (ref "U5") (pin "109") (pinfunction "PA_10_109") (pintype "bidirectional"))
    )
    (net (code "152") (name "unconnected-(U5-VBAT-Pad18)") (class "Default")
      (node (ref "U5") (pin "18") (pinfunction "VBAT_18") (pintype "bidirectional"))
    )
    (net (code "153") (name "unconnected-(U5-VREFH-Pad154)") (class "Default")
      (node (ref "U5") (pin "154") (pinfunction "VREFH_154") (pintype "bidirectional"))
    )
    (net (code "154") (name "unconnected-(U5-VREFH0-Pad158)") (class "Default")
      (node (ref "U5") (pin "158") (pinfunction "VREFH0_158") (pintype "bidirectional"))
    )
    (net (code "155") (name "unconnected-(U5-VREFL-Pad153)") (class "Default")
      (node (ref "U5") (pin "153") (pinfunction "VREFL_153") (pintype "bidirectional"))
    )
    (net (code "156") (name "unconnected-(U5-VREFL0-Pad157)") (class "Default")
      (node (ref "U5") (pin "157") (pinfunction "VREFL0_157") (pintype "bidirectional"))
    )
  )
)
